# GankenKunCircuit.net
KiCad netlist of a schematic drawn in EAGLE
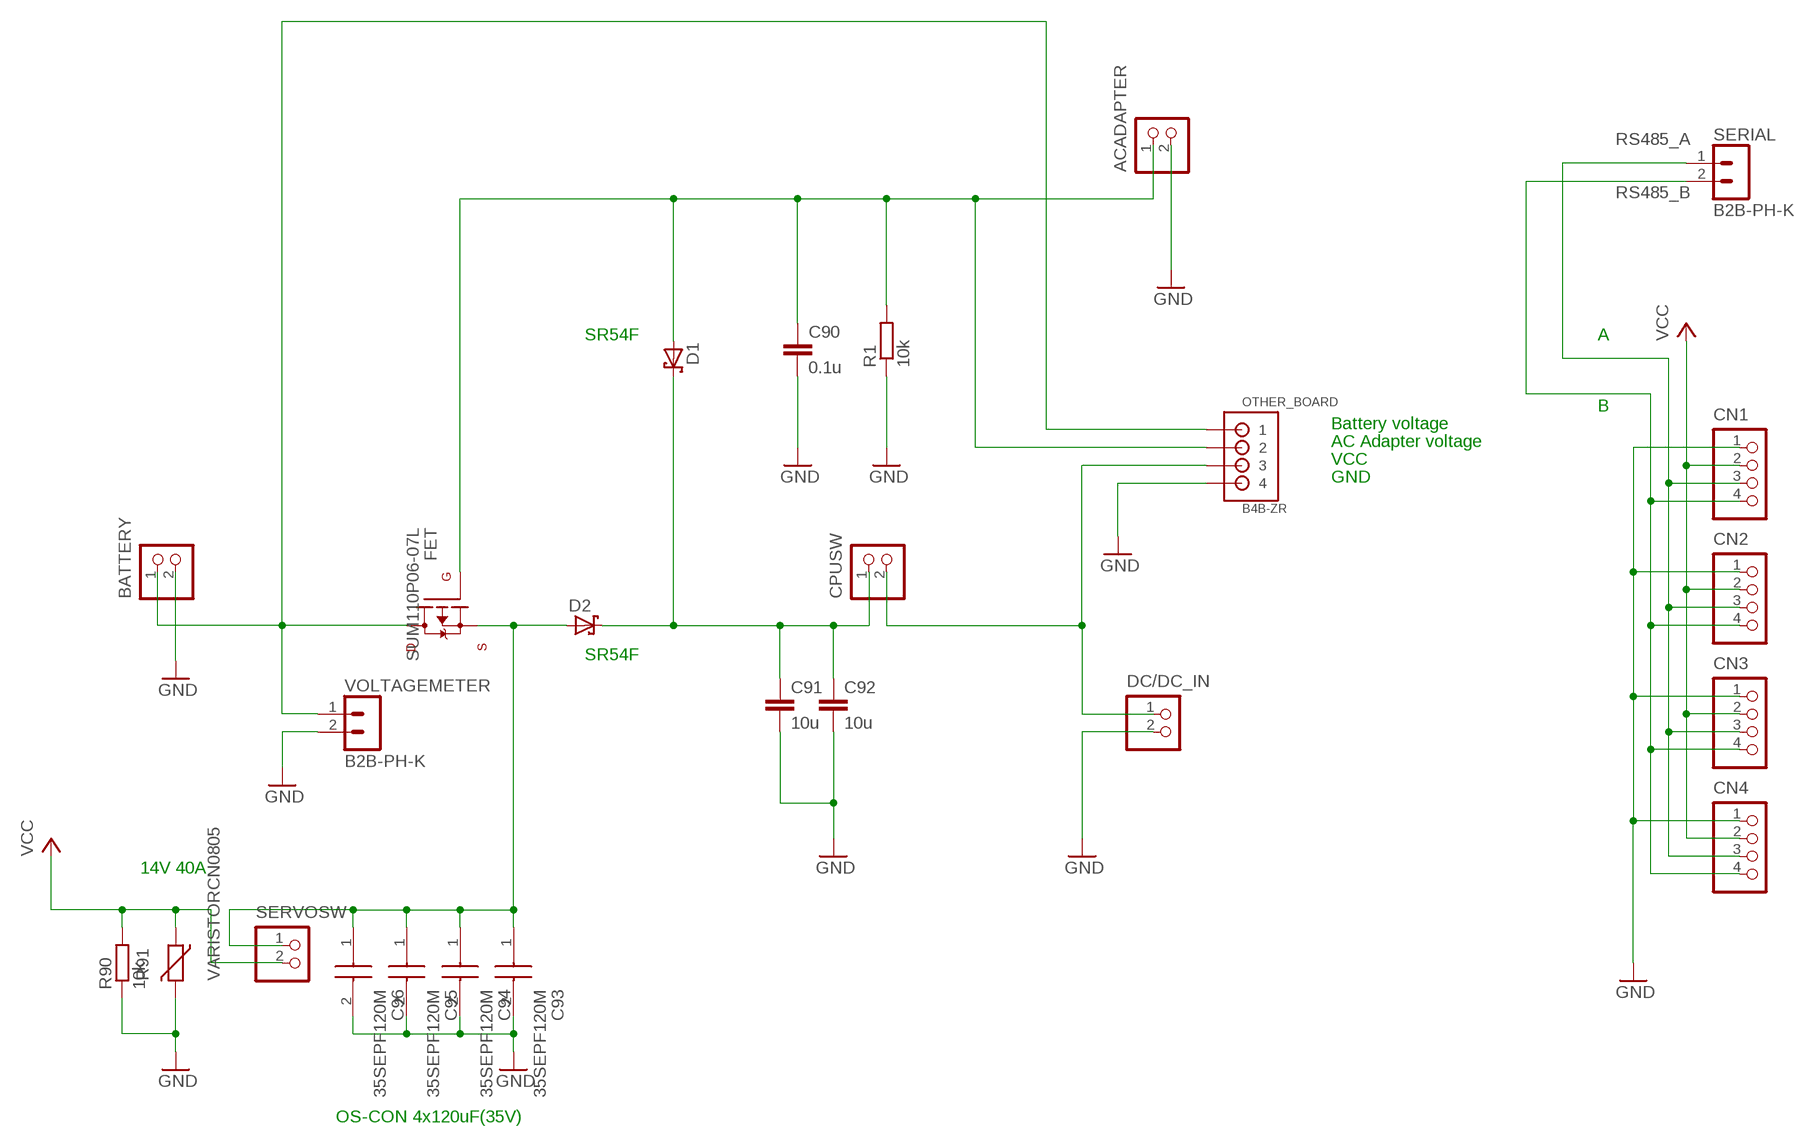
[diagram p0: schematic, sheet 1]

(export (version "E")
  (design (tool "Eeschema 10.0.6"))
  (components
    (comp (ref "ACADAPTER")
      (value "B2B-XH-A")
      (footprint "eagle-import:B2B-XH-A")
      (libsource (lib "eagle-import") (part "B2B-XH-A"))
    )
    (comp (ref "BATTERY")
      (value "B2P-VH")
      (footprint "eagle-import:B2P-VH")
      (libsource (lib "eagle-import") (part "B2P-VH"))
    )
    (comp (ref "C90")
      (value "0.1u")
      (footprint "eagle-import:C1608")
      (libsource (lib "eagle-import") (part "C-EUC1608"))
    )
    (comp (ref "C91")
      (value "10u")
      (footprint "eagle-import:C3216")
      (libsource (lib "eagle-import") (part "C-EUC3216"))
    )
    (comp (ref "C92")
      (value "10u")
      (footprint "eagle-import:C3216")
      (libsource (lib "eagle-import") (part "C-EUC3216"))
    )
    (comp (ref "C93")
      (value "35SEPF120M")
      (footprint "eagle-import:CAPPRD500W65D1000H1350")
      (fields (field (name "MOUSER_PART_NUMBER") "667-35SEPF120M") (field (name "RS_PART_NUMBER") "1000082"))
      (libsource (lib "eagle-import") (part "35SEPF120M"))
    )
    (comp (ref "C94")
      (value "35SEPF120M")
      (footprint "eagle-import:CAPPRD500W65D1000H1350")
      (fields (field (name "MOUSER_PART_NUMBER") "667-35SEPF120M") (field (name "RS_PART_NUMBER") "1000082"))
      (libsource (lib "eagle-import") (part "35SEPF120M"))
    )
    (comp (ref "C95")
      (value "35SEPF120M")
      (footprint "eagle-import:CAPPRD500W65D1000H1350")
      (fields (field (name "MOUSER_PART_NUMBER") "667-35SEPF120M") (field (name "RS_PART_NUMBER") "1000082"))
      (libsource (lib "eagle-import") (part "35SEPF120M"))
    )
    (comp (ref "C96")
      (value "35SEPF120M")
      (footprint "eagle-import:CAPPRD500W65D1000H1350")
      (fields (field (name "MOUSER_PART_NUMBER") "667-35SEPF120M") (field (name "RS_PART_NUMBER") "1000082"))
      (libsource (lib "eagle-import") (part "35SEPF120M"))
    )
    (comp (ref "CN1")
      (value "B4B-XH-A")
      (footprint "eagle-import:B4B-XH-A")
      (libsource (lib "eagle-import") (part "B4B-XH-A"))
    )
    (comp (ref "CN2")
      (value "B4B-XH-A")
      (footprint "eagle-import:B4B-XH-A")
      (libsource (lib "eagle-import") (part "B4B-XH-A"))
    )
    (comp (ref "CN3")
      (value "B4B-XH-A")
      (footprint "eagle-import:B4B-XH-A")
      (libsource (lib "eagle-import") (part "B4B-XH-A"))
    )
    (comp (ref "CN4")
      (value "B4B-XH-A")
      (footprint "eagle-import:B4B-XH-A")
      (libsource (lib "eagle-import") (part "B4B-XH-A"))
    )
    (comp (ref "CPUSW")
      (value "B2B-XH-A")
      (footprint "eagle-import:B2B-XH-A")
      (libsource (lib "eagle-import") (part "B2B-XH-A"))
    )
    (comp (ref "D1")
      (value "SCHOTTKY-DIODESMD")
      (footprint "eagle-import:SMB")
      (libsource (lib "eagle-import") (part "SCHOTTKY-DIODESMD"))
    )
    (comp (ref "D2")
      (value "SCHOTTKY-DIODESMD")
      (footprint "eagle-import:SMB")
      (libsource (lib "eagle-import") (part "SCHOTTKY-DIODESMD"))
    )
    (comp (ref "DC/DC_IN")
      (value "B2B-XH-A")
      (footprint "eagle-import:B2B-XH-A")
      (libsource (lib "eagle-import") (part "B2B-XH-A"))
    )
    (comp (ref "FET")
      (value "SUM110P06-07L")
      (footprint "eagle-import:TO-263-2")
      (fields (field (name "MF") "Vishay"))
      (libsource (lib "eagle-import") (part "SUM110P06-07L"))
    )
    (comp (ref "OTHER_BOARD")
      (value "B4B-ZR")
      (footprint "eagle-import:B4B-ZR")
      (libsource (lib "eagle-import") (part "B4B-ZR"))
    )
    (comp (ref "R1")
      (value "10k")
      (footprint "eagle-import:R0603")
      (libsource (lib "eagle-import") (part "R-EU_R0603"))
    )
    (comp (ref "R90")
      (value "10k")
      (footprint "eagle-import:R0603")
      (libsource (lib "eagle-import") (part "R-EU_R0603"))
    )
    (comp (ref "R91")
      (value "VARISTORCN0805")
      (footprint "eagle-import:CT_CN0805")
      (libsource (lib "eagle-import") (part "VARISTORCN0805"))
    )
    (comp (ref "SERIAL")
      (value "B2B-PH-K")
      (footprint "eagle-import:B2B-PH-K")
      (libsource (lib "eagle-import") (part "B2B-PH-K"))
    )
    (comp (ref "SERVOSW")
      (value "B2P-VH")
      (footprint "eagle-import:B2P-VH")
      (libsource (lib "eagle-import") (part "B2P-VH"))
    )
    (comp (ref "VOLTAGEMETER")
      (value "B2B-PH-K")
      (footprint "eagle-import:B2B-PH-K")
      (libsource (lib "eagle-import") (part "B2B-PH-K"))
    )
  )
  (nets
    (net (code "1") (name "/RS485_A") (class "Default")
      (node (ref "CN1") (pin "3") (pinfunction "3_3") (pintype "passive"))
      (node (ref "CN2") (pin "3") (pinfunction "3_3") (pintype "passive"))
      (node (ref "CN3") (pin "3") (pinfunction "3_3") (pintype "passive"))
      (node (ref "CN4") (pin "3") (pinfunction "3_3") (pintype "passive"))
      (node (ref "SERIAL") (pin "1") (pinfunction "1_1") (pintype "passive"))
    )
    (net (code "2") (name "/RS485_B") (class "Default")
      (node (ref "CN1") (pin "4") (pinfunction "4_4") (pintype "passive"))
      (node (ref "CN2") (pin "4") (pinfunction "4_4") (pintype "passive"))
      (node (ref "CN3") (pin "4") (pinfunction "4_4") (pintype "passive"))
      (node (ref "CN4") (pin "4") (pinfunction "4_4") (pintype "passive"))
      (node (ref "SERIAL") (pin "2") (pinfunction "2_2") (pintype "passive"))
    )
    (net (code "3") (name "GND") (class "Default")
      (node (ref "ACADAPTER") (pin "2") (pinfunction "2_2") (pintype "passive"))
      (node (ref "BATTERY") (pin "2") (pinfunction "2_2") (pintype "passive"))
      (node (ref "C90") (pin "2") (pinfunction "2_2") (pintype "passive"))
      (node (ref "C91") (pin "2") (pinfunction "2_2") (pintype "passive"))
      (node (ref "C92") (pin "2") (pinfunction "2_2") (pintype "passive"))
      (node (ref "C93") (pin "2") (pinfunction "-_2") (pintype "bidirectional"))
      (node (ref "C94") (pin "2") (pinfunction "-_2") (pintype "bidirectional"))
      (node (ref "C95") (pin "2") (pinfunction "-_2") (pintype "bidirectional"))
      (node (ref "C96") (pin "2") (pinfunction "-_2") (pintype "bidirectional"))
      (node (ref "CN1") (pin "1") (pinfunction "1_1") (pintype "passive"))
      (node (ref "CN2") (pin "1") (pinfunction "1_1") (pintype "passive"))
      (node (ref "CN3") (pin "1") (pinfunction "1_1") (pintype "passive"))
      (node (ref "CN4") (pin "1") (pinfunction "1_1") (pintype "passive"))
      (node (ref "DC/DC_IN") (pin "2") (pinfunction "2_2") (pintype "passive"))
      (node (ref "OTHER_BOARD") (pin "4") (pinfunction "4_4") (pintype "bidirectional"))
      (node (ref "R1") (pin "1") (pinfunction "1_1") (pintype "passive"))
      (node (ref "R90") (pin "1") (pinfunction "1_1") (pintype "passive"))
      (node (ref "R91") (pin "2") (pinfunction "2_2") (pintype "passive"))
      (node (ref "VOLTAGEMETER") (pin "2") (pinfunction "2_2") (pintype "passive"))
    )
    (net (code "4") (name "Net-(C91-Pad1)") (class "Default")
      (node (ref "C91") (pin "1") (pinfunction "1_1") (pintype "passive"))
      (node (ref "C92") (pin "1") (pinfunction "1_1") (pintype "passive"))
      (node (ref "CPUSW") (pin "1") (pinfunction "1_1") (pintype "passive"))
      (node (ref "D1") (pin "C") (pinfunction "C_C") (pintype "passive"))
      (node (ref "D2") (pin "C") (pinfunction "C_C") (pintype "passive"))
    )
    (net (code "5") (name "Net-(C93-+)") (class "Default")
      (node (ref "C93") (pin "1") (pinfunction "+_1") (pintype "bidirectional"))
      (node (ref "C94") (pin "1") (pinfunction "+_1") (pintype "bidirectional"))
      (node (ref "C95") (pin "1") (pinfunction "+_1") (pintype "bidirectional"))
      (node (ref "C96") (pin "1") (pinfunction "+_1") (pintype "bidirectional"))
      (node (ref "D2") (pin "A") (pinfunction "A_A") (pintype "passive"))
      (node (ref "FET") (pin "3") (pinfunction "S_3") (pintype "passive"))
      (node (ref "SERVOSW") (pin "1") (pinfunction "1_1") (pintype "passive"))
    )
    (net (code "6") (name "Net-(CPUSW-Pad2)") (class "Default")
      (node (ref "CPUSW") (pin "2") (pinfunction "2_2") (pintype "passive"))
      (node (ref "DC/DC_IN") (pin "1") (pinfunction "1_1") (pintype "passive"))
      (node (ref "OTHER_BOARD") (pin "3") (pinfunction "3_3") (pintype "bidirectional"))
    )
    (net (code "7") (name "Net-(FET-D)") (class "Default")
      (node (ref "BATTERY") (pin "1") (pinfunction "1_1") (pintype "passive"))
      (node (ref "FET") (pin "4") (pinfunction "D_4") (pintype "passive"))
      (node (ref "OTHER_BOARD") (pin "1") (pinfunction "1_1") (pintype "bidirectional"))
      (node (ref "VOLTAGEMETER") (pin "1") (pinfunction "1_1") (pintype "passive"))
    )
    (net (code "8") (name "Net-(FET-G)") (class "Default")
      (node (ref "ACADAPTER") (pin "1") (pinfunction "1_1") (pintype "passive"))
      (node (ref "C90") (pin "1") (pinfunction "1_1") (pintype "passive"))
      (node (ref "D1") (pin "A") (pinfunction "A_A") (pintype "passive"))
      (node (ref "FET") (pin "1") (pinfunction "G_1") (pintype "passive"))
      (node (ref "OTHER_BOARD") (pin "2") (pinfunction "2_2") (pintype "bidirectional"))
      (node (ref "R1") (pin "2") (pinfunction "2_2") (pintype "passive"))
    )
    (net (code "9") (name "VCC") (class "Default")
      (node (ref "CN1") (pin "2") (pinfunction "2_2") (pintype "passive"))
      (node (ref "CN2") (pin "2") (pinfunction "2_2") (pintype "passive"))
      (node (ref "CN3") (pin "2") (pinfunction "2_2") (pintype "passive"))
      (node (ref "CN4") (pin "2") (pinfunction "2_2") (pintype "passive"))
      (node (ref "R90") (pin "2") (pinfunction "2_2") (pintype "passive"))
      (node (ref "R91") (pin "1") (pinfunction "1_1") (pintype "passive"))
      (node (ref "SERVOSW") (pin "2") (pinfunction "2_2") (pintype "passive"))
    )
  )
)
